# IHM.net
KiCad netlist of a schematic drawn in Altium Designer
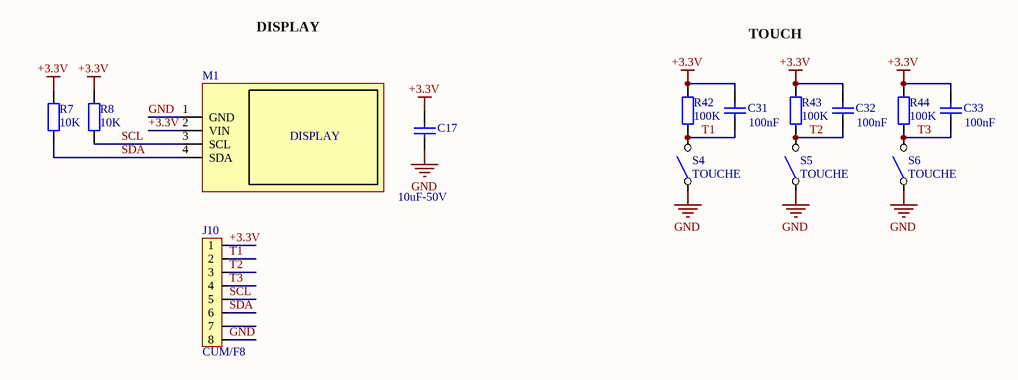
[diagram p0: IHM.SchDoc]

(export (version "E")
  (design (tool "Eeschema 10.0.6"))
  (components
    (comp (ref "C17")
      (value "10uF-50V")
      (footprint "C1206")
      (description "Capacitor")
      (libsource (lib "MyLibrary") (part "Cap"))
    )
    (comp (ref "C31")
      (value "100nF")
      (footprint "C0603")
      (description "Capacitor")
      (libsource (lib "MyLibrary") (part "Cap"))
    )
    (comp (ref "C32")
      (value "100nF")
      (footprint "C0603")
      (description "Capacitor")
      (libsource (lib "MyLibrary") (part "Cap"))
    )
    (comp (ref "C33")
      (value "100nF")
      (footprint "C0603")
      (description "Capacitor")
      (libsource (lib "MyLibrary") (part "Cap"))
    )
    (comp (ref "J10")
      (value "CUM/F8")
      (footprint "BARF-2X4")
      (description "connecteur 8 points")
      (libsource (lib "PROTEL") (part "CUM/F8"))
    )
    (comp (ref "M1")
      (value "~")
      (footprint "I2C_OLED_0.96")
      (description "I2C OLED 0.96\"")
      (libsource (lib "MyLibrary") (part "I2C-OLED-0.96"))
    )
    (comp (ref "R7")
      (value "10K")
      (footprint "R0603")
      (description "Thin Metal Film Resistor")
      (libsource (lib "MyLibrary") (part "Res"))
    )
    (comp (ref "R8")
      (value "10K")
      (footprint "R0603")
      (description "Thin Metal Film Resistor")
      (libsource (lib "MyLibrary") (part "Res"))
    )
    (comp (ref "R42")
      (value "100K")
      (footprint "R0603")
      (description "Thin Metal Film Resistor")
      (libsource (lib "MyLibrary") (part "Res"))
    )
    (comp (ref "R43")
      (value "100K")
      (footprint "R0603")
      (description "Thin Metal Film Resistor")
      (libsource (lib "MyLibrary") (part "Res"))
    )
    (comp (ref "R44")
      (value "100K")
      (footprint "R0603")
      (description "Thin Metal Film Resistor")
      (libsource (lib "MyLibrary") (part "Res"))
    )
    (comp (ref "S4")
      (value "TOUCHE")
      (footprint "INT-CMS1")
      (description "Touche")
      (libsource (lib "PROTEL") (part "TOUCHE"))
    )
    (comp (ref "S5")
      (value "TOUCHE")
      (footprint "INT-CMS1")
      (description "Touche")
      (libsource (lib "PROTEL") (part "TOUCHE"))
    )
    (comp (ref "S6")
      (value "TOUCHE")
      (footprint "INT-CMS1")
      (description "Touche")
      (libsource (lib "PROTEL") (part "TOUCHE"))
    )
  )
  (nets
    (net (code "1") (name "+3.3V") (class "Default")
      (node (ref "C17") (pin "2") (pinfunction "2_2") (pintype "passive"))
      (node (ref "C31") (pin "2") (pinfunction "2_2") (pintype "passive"))
      (node (ref "C32") (pin "2") (pinfunction "2_2") (pintype "passive"))
      (node (ref "C33") (pin "2") (pinfunction "2_2") (pintype "passive"))
      (node (ref "J10") (pin "1") (pinfunction "1_1") (pintype "passive"))
      (node (ref "M1") (pin "2") (pinfunction "VIN_2") (pintype "power_in"))
      (node (ref "R42") (pin "2") (pinfunction "2_2") (pintype "passive"))
      (node (ref "R43") (pin "2") (pinfunction "2_2") (pintype "passive"))
      (node (ref "R44") (pin "2") (pinfunction "2_2") (pintype "passive"))
      (node (ref "R7") (pin "2") (pinfunction "2_2") (pintype "passive"))
      (node (ref "R8") (pin "2") (pinfunction "2_2") (pintype "passive"))
    )
    (net (code "2") (name "/SCL") (class "Default")
      (node (ref "J10") (pin "5") (pinfunction "5_5") (pintype "passive"))
      (node (ref "M1") (pin "3") (pinfunction "SCL_3") (pintype "power_in"))
      (node (ref "R8") (pin "1") (pinfunction "1_1") (pintype "passive"))
    )
    (net (code "3") (name "/SDA") (class "Default")
      (node (ref "J10") (pin "6") (pinfunction "6_6") (pintype "passive"))
      (node (ref "M1") (pin "4") (pinfunction "SDA_4") (pintype "power_in"))
      (node (ref "R7") (pin "1") (pinfunction "1_1") (pintype "passive"))
    )
    (net (code "4") (name "/T1") (class "Default")
      (node (ref "C31") (pin "1") (pinfunction "1_1") (pintype "passive"))
      (node (ref "J10") (pin "2") (pinfunction "2_2") (pintype "passive"))
      (node (ref "R42") (pin "1") (pinfunction "1_1") (pintype "passive"))
      (node (ref "S4") (pin "4") (pinfunction "4_4") (pintype "passive"))
    )
    (net (code "5") (name "/T2") (class "Default")
      (node (ref "C32") (pin "1") (pinfunction "1_1") (pintype "passive"))
      (node (ref "J10") (pin "3") (pinfunction "3_3") (pintype "passive"))
      (node (ref "R43") (pin "1") (pinfunction "1_1") (pintype "passive"))
      (node (ref "S5") (pin "4") (pinfunction "4_4") (pintype "passive"))
    )
    (net (code "6") (name "/T3") (class "Default")
      (node (ref "C33") (pin "1") (pinfunction "1_1") (pintype "passive"))
      (node (ref "J10") (pin "4") (pinfunction "4_4") (pintype "passive"))
      (node (ref "R44") (pin "1") (pinfunction "1_1") (pintype "passive"))
      (node (ref "S6") (pin "4") (pinfunction "4_4") (pintype "passive"))
    )
    (net (code "7") (name "GND") (class "Default")
      (node (ref "C17") (pin "1") (pinfunction "1_1") (pintype "passive"))
      (node (ref "J10") (pin "8") (pinfunction "8_8") (pintype "passive"))
      (node (ref "M1") (pin "1") (pinfunction "GND_1") (pintype "power_in"))
      (node (ref "S4") (pin "1") (pinfunction "1_1") (pintype "passive"))
      (node (ref "S5") (pin "1") (pinfunction "1_1") (pintype "passive"))
      (node (ref "S6") (pin "1") (pinfunction "1_1") (pintype "passive"))
    )
    (net (code "8") (name "unconnected-(J10-Pad7)") (class "Default")
      (node (ref "J10") (pin "7") (pinfunction "7_7") (pintype "passive"))
    )
  )
)
